# TDFN-14_with_EP_to_DIP-15.net
KiCad netlist of a schematic drawn in EAGLE
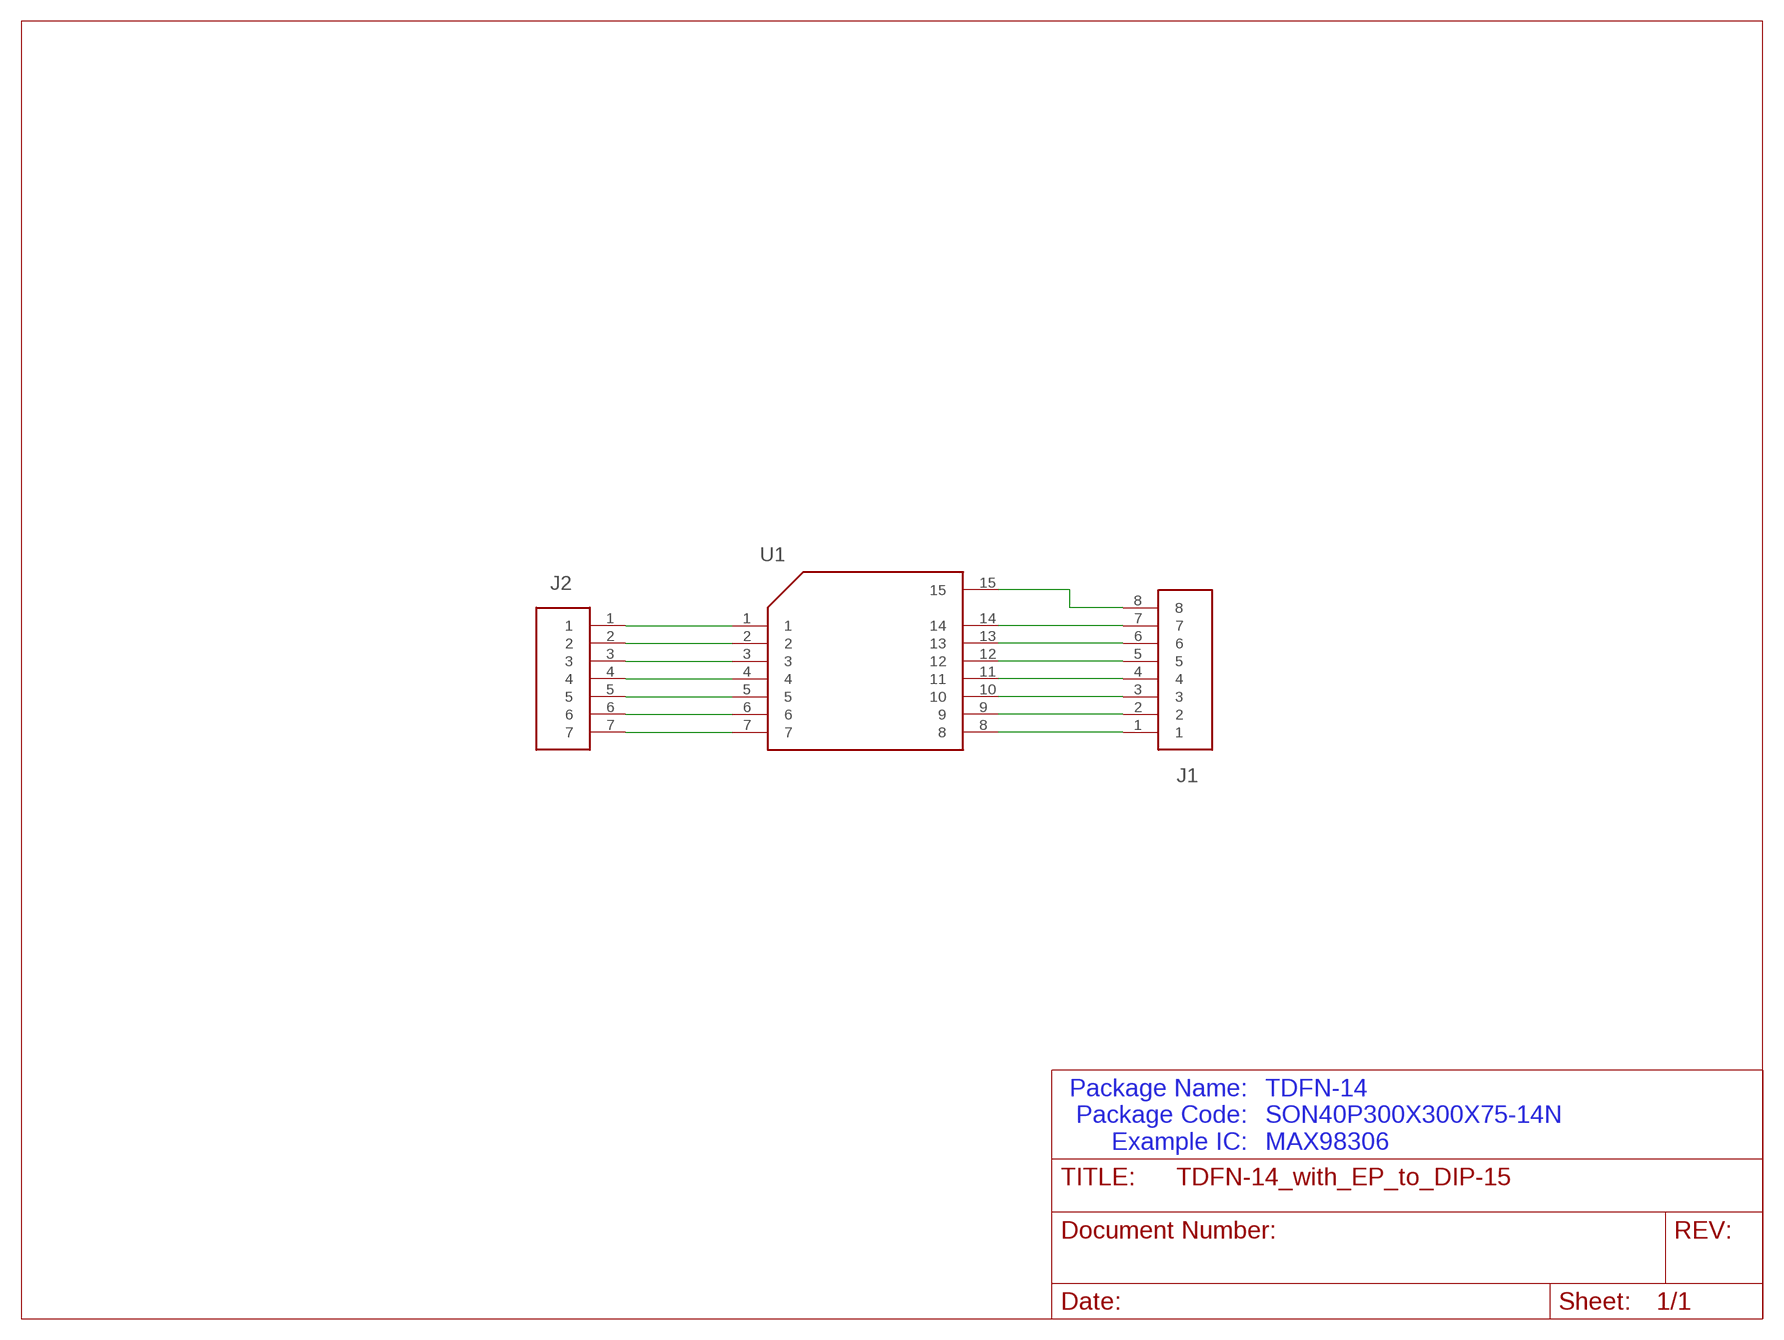
[diagram p0: schematic, sheet 1]

(export (version "E")
  (design (tool "Eeschema 10.0.6"))
  (components
    (comp (ref "J1")
      (value "CONNECTOR_8-NO_SQUARE")
      (footprint "eagle-import:68000-108HLF-NO-SQUARE")
      (libsource (lib "eagle-import") (part "CONNECTOR_8-NO_SQUARE"))
    )
    (comp (ref "J2")
      (value "CONNECTOR_7")
      (footprint "eagle-import:68000-107HLF")
      (libsource (lib "eagle-import") (part "CONNECTOR_7"))
    )
    (comp (ref "U1")
      (value "IC_GENERIC_14_PLUS_EP-DFN-14_PLUS_EP")
      (footprint "eagle-import:SON40P300X300X75-14N")
      (libsource (lib "eagle-import") (part "IC_GENERIC_14_PLUS_EP-DFN-14_PLUS_EP"))
    )
  )
  (nets
    (net (code "1") (name "Net-(J1-Pad1)") (class "Default")
      (node (ref "J1") (pin "1") (pinfunction "1_1") (pintype "bidirectional"))
      (node (ref "U1") (pin "8") (pinfunction "8_8") (pintype "bidirectional"))
    )
    (net (code "2") (name "Net-(J1-Pad2)") (class "Default")
      (node (ref "J1") (pin "2") (pinfunction "2_2") (pintype "bidirectional"))
      (node (ref "U1") (pin "9") (pinfunction "9_9") (pintype "bidirectional"))
    )
    (net (code "3") (name "Net-(J1-Pad3)") (class "Default")
      (node (ref "J1") (pin "3") (pinfunction "3_3") (pintype "bidirectional"))
      (node (ref "U1") (pin "10") (pinfunction "10_10") (pintype "bidirectional"))
    )
    (net (code "4") (name "Net-(J1-Pad4)") (class "Default")
      (node (ref "J1") (pin "4") (pinfunction "4_4") (pintype "bidirectional"))
      (node (ref "U1") (pin "11") (pinfunction "11_11") (pintype "bidirectional"))
    )
    (net (code "5") (name "Net-(J1-Pad5)") (class "Default")
      (node (ref "J1") (pin "5") (pinfunction "5_5") (pintype "bidirectional"))
      (node (ref "U1") (pin "12") (pinfunction "12_12") (pintype "bidirectional"))
    )
    (net (code "6") (name "Net-(J1-Pad6)") (class "Default")
      (node (ref "J1") (pin "6") (pinfunction "6_6") (pintype "bidirectional"))
      (node (ref "U1") (pin "13") (pinfunction "13_13") (pintype "bidirectional"))
    )
    (net (code "7") (name "Net-(J1-Pad7)") (class "Default")
      (node (ref "J1") (pin "7") (pinfunction "7_7") (pintype "bidirectional"))
      (node (ref "U1") (pin "14") (pinfunction "14_14") (pintype "bidirectional"))
    )
    (net (code "8") (name "Net-(J1-Pad8)") (class "Default")
      (node (ref "J1") (pin "8") (pinfunction "8_8") (pintype "bidirectional"))
      (node (ref "U1") (pin "15") (pinfunction "15_15") (pintype "bidirectional"))
    )
    (net (code "9") (name "Net-(J2-Pad1)") (class "Default")
      (node (ref "J2") (pin "1") (pinfunction "1_1") (pintype "bidirectional"))
      (node (ref "U1") (pin "1") (pinfunction "1_1") (pintype "bidirectional"))
    )
    (net (code "10") (name "Net-(J2-Pad2)") (class "Default")
      (node (ref "J2") (pin "2") (pinfunction "2_2") (pintype "bidirectional"))
      (node (ref "U1") (pin "2") (pinfunction "2_2") (pintype "bidirectional"))
    )
    (net (code "11") (name "Net-(J2-Pad3)") (class "Default")
      (node (ref "J2") (pin "3") (pinfunction "3_3") (pintype "bidirectional"))
      (node (ref "U1") (pin "3") (pinfunction "3_3") (pintype "bidirectional"))
    )
    (net (code "12") (name "Net-(J2-Pad4)") (class "Default")
      (node (ref "J2") (pin "4") (pinfunction "4_4") (pintype "bidirectional"))
      (node (ref "U1") (pin "4") (pinfunction "4_4") (pintype "bidirectional"))
    )
    (net (code "13") (name "Net-(J2-Pad5)") (class "Default")
      (node (ref "J2") (pin "5") (pinfunction "5_5") (pintype "bidirectional"))
      (node (ref "U1") (pin "5") (pinfunction "5_5") (pintype "bidirectional"))
    )
    (net (code "14") (name "Net-(J2-Pad6)") (class "Default")
      (node (ref "J2") (pin "6") (pinfunction "6_6") (pintype "bidirectional"))
      (node (ref "U1") (pin "6") (pinfunction "6_6") (pintype "bidirectional"))
    )
    (net (code "15") (name "Net-(J2-Pad7)") (class "Default")
      (node (ref "J2") (pin "7") (pinfunction "7_7") (pintype "bidirectional"))
      (node (ref "U1") (pin "7") (pinfunction "7_7") (pintype "bidirectional"))
    )
  )
)
